# Power.net
KiCad netlist of a schematic drawn in Altium Designer
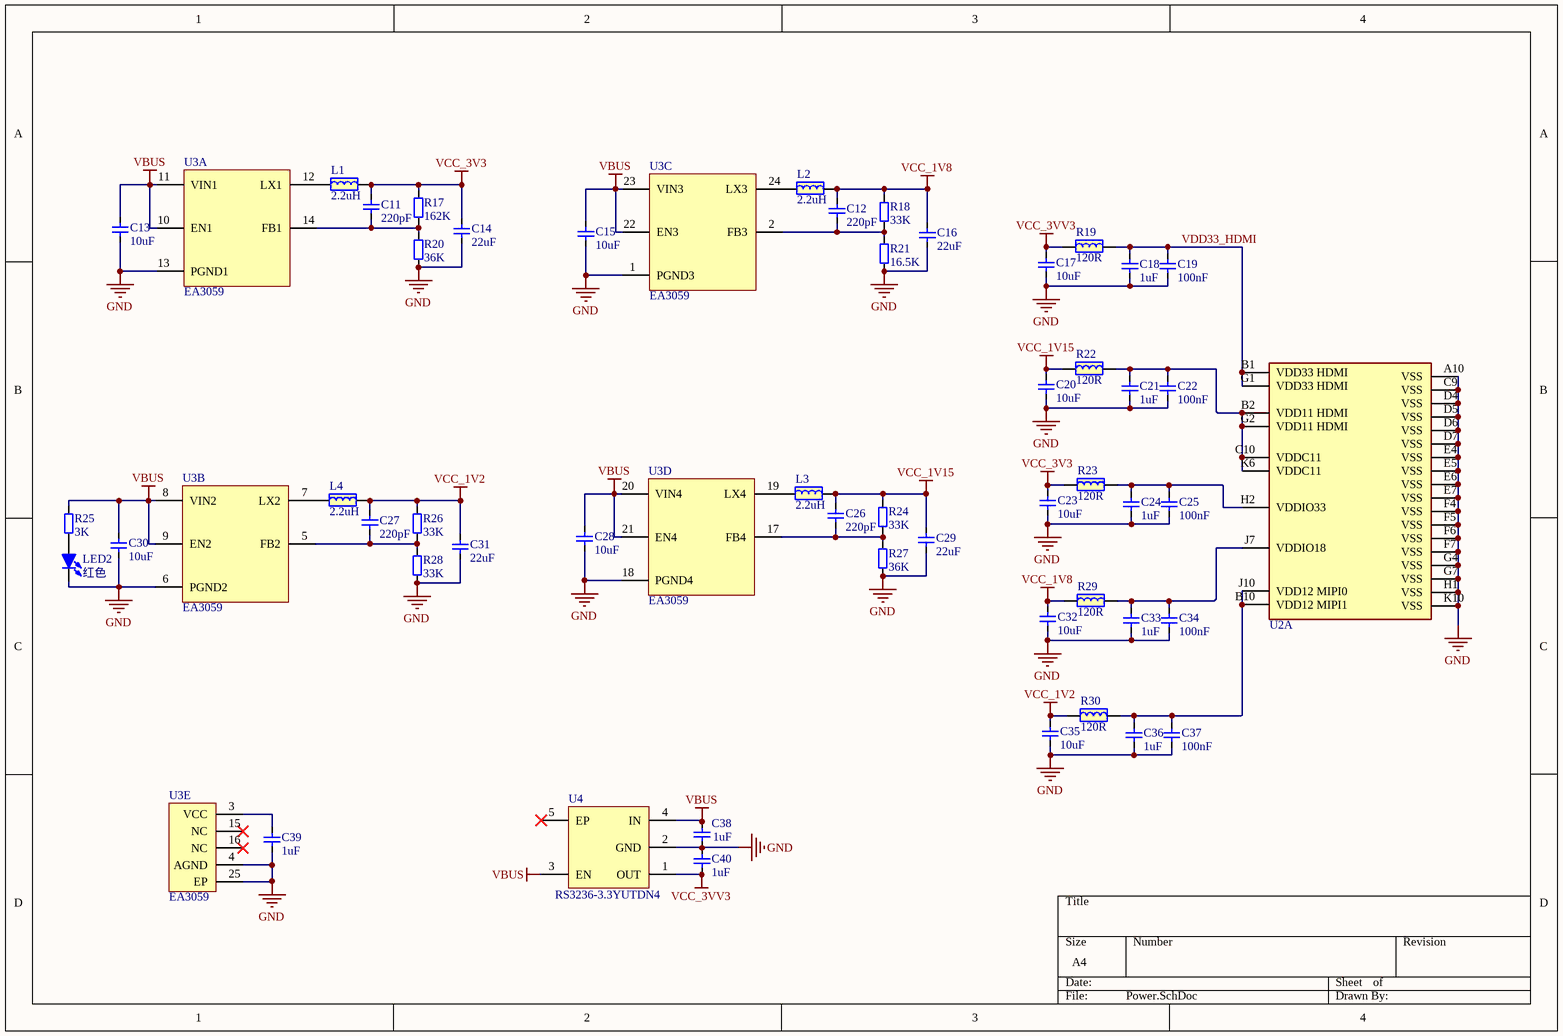
[diagram p0: Power.SchDoc]

(export (version "E")
  (design (tool "Eeschema 10.0.6"))
  (components
    (comp (ref "C11")
      (value "220pF")
      (footprint "C0402_L")
      (description "贴片电容")
      (libsource (lib "0.1 - 电阻-电容-电感-磁珠-电位器") (part "C"))
    )
    (comp (ref "C12")
      (value "220pF")
      (footprint "C0402_L")
      (description "贴片电容")
      (libsource (lib "0.1 - 电阻-电容-电感-磁珠-电位器") (part "C"))
    )
    (comp (ref "C13")
      (value "10uF")
      (footprint "C0402_L")
      (description "贴片电容")
      (libsource (lib "0.1 - 电阻-电容-电感-磁珠-电位器") (part "C"))
    )
    (comp (ref "C14")
      (value "22uF")
      (footprint "C0402_L")
      (description "贴片电容")
      (libsource (lib "0.1 - 电阻-电容-电感-磁珠-电位器") (part "C"))
    )
    (comp (ref "C15")
      (value "10uF")
      (footprint "C0402_L")
      (description "贴片电容")
      (libsource (lib "0.1 - 电阻-电容-电感-磁珠-电位器") (part "C"))
    )
    (comp (ref "C16")
      (value "22uF")
      (footprint "C0402_L")
      (description "贴片电容")
      (libsource (lib "0.1 - 电阻-电容-电感-磁珠-电位器") (part "C"))
    )
    (comp (ref "C17")
      (value "10uF")
      (footprint "C0402_L")
      (description "贴片电容")
      (libsource (lib "0.1 - 电阻-电容-电感-磁珠-电位器") (part "C"))
    )
    (comp (ref "C18")
      (value "1uF")
      (footprint "C0402_L")
      (description "贴片电容")
      (libsource (lib "0.1 - 电阻-电容-电感-磁珠-电位器") (part "C"))
    )
    (comp (ref "C19")
      (value "100nF")
      (footprint "C0402_L")
      (description "贴片电容")
      (libsource (lib "0.1 - 电阻-电容-电感-磁珠-电位器") (part "C"))
    )
    (comp (ref "C20")
      (value "10uF")
      (footprint "C0402_L")
      (description "贴片电容")
      (libsource (lib "0.1 - 电阻-电容-电感-磁珠-电位器") (part "C"))
    )
    (comp (ref "C21")
      (value "1uF")
      (footprint "C0402_L")
      (description "贴片电容")
      (libsource (lib "0.1 - 电阻-电容-电感-磁珠-电位器") (part "C"))
    )
    (comp (ref "C22")
      (value "100nF")
      (footprint "C0402_L")
      (description "贴片电容")
      (libsource (lib "0.1 - 电阻-电容-电感-磁珠-电位器") (part "C"))
    )
    (comp (ref "C23")
      (value "10uF")
      (footprint "C0402_L")
      (description "贴片电容")
      (libsource (lib "0.1 - 电阻-电容-电感-磁珠-电位器") (part "C"))
    )
    (comp (ref "C24")
      (value "1uF")
      (footprint "C0402_L")
      (description "贴片电容")
      (libsource (lib "0.1 - 电阻-电容-电感-磁珠-电位器") (part "C"))
    )
    (comp (ref "C25")
      (value "100nF")
      (footprint "C0402_L")
      (description "贴片电容")
      (libsource (lib "0.1 - 电阻-电容-电感-磁珠-电位器") (part "C"))
    )
    (comp (ref "C26")
      (value "220pF")
      (footprint "C0402_L")
      (description "贴片电容")
      (libsource (lib "0.1 - 电阻-电容-电感-磁珠-电位器") (part "C"))
    )
    (comp (ref "C27")
      (value "220pF")
      (footprint "C0402_L")
      (description "贴片电容")
      (libsource (lib "0.1 - 电阻-电容-电感-磁珠-电位器") (part "C"))
    )
    (comp (ref "C28")
      (value "10uF")
      (footprint "C0402_L")
      (description "贴片电容")
      (libsource (lib "0.1 - 电阻-电容-电感-磁珠-电位器") (part "C"))
    )
    (comp (ref "C29")
      (value "22uF")
      (footprint "C0402_L")
      (description "贴片电容")
      (libsource (lib "0.1 - 电阻-电容-电感-磁珠-电位器") (part "C"))
    )
    (comp (ref "C30")
      (value "10uF")
      (footprint "C0402_L")
      (description "贴片电容")
      (libsource (lib "0.1 - 电阻-电容-电感-磁珠-电位器") (part "C"))
    )
    (comp (ref "C31")
      (value "22uF")
      (footprint "C0402_L")
      (description "贴片电容")
      (libsource (lib "0.1 - 电阻-电容-电感-磁珠-电位器") (part "C"))
    )
    (comp (ref "C32")
      (value "10uF")
      (footprint "C0402_L")
      (description "贴片电容")
      (libsource (lib "0.1 - 电阻-电容-电感-磁珠-电位器") (part "C"))
    )
    (comp (ref "C33")
      (value "1uF")
      (footprint "C0402_L")
      (description "贴片电容")
      (libsource (lib "0.1 - 电阻-电容-电感-磁珠-电位器") (part "C"))
    )
    (comp (ref "C34")
      (value "100nF")
      (footprint "C0402_L")
      (description "贴片电容")
      (libsource (lib "0.1 - 电阻-电容-电感-磁珠-电位器") (part "C"))
    )
    (comp (ref "C35")
      (value "10uF")
      (footprint "C0402_L")
      (description "贴片电容")
      (libsource (lib "0.1 - 电阻-电容-电感-磁珠-电位器") (part "C"))
    )
    (comp (ref "C36")
      (value "1uF")
      (footprint "C0402_L")
      (description "贴片电容")
      (libsource (lib "0.1 - 电阻-电容-电感-磁珠-电位器") (part "C"))
    )
    (comp (ref "C37")
      (value "100nF")
      (footprint "C0402_L")
      (description "贴片电容")
      (libsource (lib "0.1 - 电阻-电容-电感-磁珠-电位器") (part "C"))
    )
    (comp (ref "C38")
      (value "1uF")
      (footprint "C0402_L")
      (description "贴片电容")
      (libsource (lib "0.1 - 电阻-电容-电感-磁珠-电位器") (part "C"))
    )
    (comp (ref "C39")
      (value "1uF")
      (footprint "C0402_L")
      (description "贴片电容")
      (libsource (lib "0.1 - 电阻-电容-电感-磁珠-电位器") (part "C"))
    )
    (comp (ref "C40")
      (value "1uF")
      (footprint "C0402_L")
      (description "贴片电容")
      (libsource (lib "0.1 - 电阻-电容-电感-磁珠-电位器") (part "C"))
    )
    (comp (ref "L1")
      (value "2.2uH")
      (footprint "L0603")
      (description "磁珠")
      (libsource (lib "0.1 - 电阻-电容-电感-磁珠-电位器") (part "L-FB"))
    )
    (comp (ref "L2")
      (value "2.2uH")
      (footprint "L0603")
      (description "磁珠")
      (libsource (lib "0.1 - 电阻-电容-电感-磁珠-电位器") (part "L-FB"))
    )
    (comp (ref "L3")
      (value "2.2uH")
      (footprint "L0603")
      (description "磁珠")
      (libsource (lib "0.1 - 电阻-电容-电感-磁珠-电位器") (part "L-FB"))
    )
    (comp (ref "L4")
      (value "2.2uH")
      (footprint "L0603")
      (description "磁珠")
      (libsource (lib "0.1 - 电阻-电容-电感-磁珠-电位器") (part "L-FB"))
    )
    (comp (ref "LED2")
      (value "红色")
      (footprint "LED0402")
      (description "贴片LED")
      (libsource (lib "0.3 - LED发光二极管") (part "LED-SMD"))
    )
    (comp (ref "R17")
      (value "162K")
      (footprint "R0402_L")
      (description "贴片电阻")
      (libsource (lib "0.1 - 电阻-电容-电感-磁珠-电位器") (part "R"))
    )
    (comp (ref "R18")
      (value "33K")
      (footprint "R0402_L")
      (description "贴片电阻")
      (libsource (lib "0.1 - 电阻-电容-电感-磁珠-电位器") (part "R"))
    )
    (comp (ref "R19")
      (value "120R")
      (footprint "L0402")
      (description "磁珠")
      (libsource (lib "0.1 - 电阻-电容-电感-磁珠-电位器") (part "L-FB"))
    )
    (comp (ref "R20")
      (value "36K")
      (footprint "R0402_L")
      (description "贴片电阻")
      (libsource (lib "0.1 - 电阻-电容-电感-磁珠-电位器") (part "R"))
    )
    (comp (ref "R21")
      (value "16.5K")
      (footprint "R0402_L")
      (description "贴片电阻")
      (libsource (lib "0.1 - 电阻-电容-电感-磁珠-电位器") (part "R"))
    )
    (comp (ref "R22")
      (value "120R")
      (footprint "L0402")
      (description "磁珠")
      (libsource (lib "0.1 - 电阻-电容-电感-磁珠-电位器") (part "L-FB"))
    )
    (comp (ref "R23")
      (value "120R")
      (footprint "L0402")
      (description "磁珠")
      (libsource (lib "0.1 - 电阻-电容-电感-磁珠-电位器") (part "L-FB"))
    )
    (comp (ref "R24")
      (value "33K")
      (footprint "R0402_L")
      (description "贴片电阻")
      (libsource (lib "0.1 - 电阻-电容-电感-磁珠-电位器") (part "R"))
    )
    (comp (ref "R25")
      (value "3K")
      (footprint "R0402_L")
      (description "贴片电阻")
      (libsource (lib "0.1 - 电阻-电容-电感-磁珠-电位器") (part "R"))
    )
    (comp (ref "R26")
      (value "33K")
      (footprint "R0402_L")
      (description "贴片电阻")
      (libsource (lib "0.1 - 电阻-电容-电感-磁珠-电位器") (part "R"))
    )
    (comp (ref "R27")
      (value "36K")
      (footprint "R0402_L")
      (description "贴片电阻")
      (libsource (lib "0.1 - 电阻-电容-电感-磁珠-电位器") (part "R"))
    )
    (comp (ref "R28")
      (value "33K")
      (footprint "R0402_L")
      (description "贴片电阻")
      (libsource (lib "0.1 - 电阻-电容-电感-磁珠-电位器") (part "R"))
    )
    (comp (ref "R29")
      (value "120R")
      (footprint "L0402")
      (description "磁珠")
      (libsource (lib "0.1 - 电阻-电容-电感-磁珠-电位器") (part "L-FB"))
    )
    (comp (ref "R30")
      (value "120R")
      (footprint "L0402")
      (description "磁珠")
      (libsource (lib "0.1 - 电阻-电容-电感-磁珠-电位器") (part "L-FB"))
    )
    (comp (ref "U2")
      (value "TC358870XBG")
      (footprint "TC358870XBG")
      (libsource (lib "User") (part "TC358870XBG"))
    )
    (comp (ref "U3")
      (value "EA3059")
      (footprint "EA3059")
      (description "4CH_BUCK")
      (libsource (lib "User") (part "EA3059"))
    )
    (comp (ref "U4")
      (value "RS3236-3.3YUTDN4")
      (footprint "RS3236-3.3YUTDN4")
      (libsource (lib "User") (part "RS3236-3.3YUTDN4"))
    )
  )
  (nets
    (net (code "1") (name "/VDD33_HDMI") (class "Default")
      (node (ref "C18") (pin "2") (pinfunction "2_2") (pintype "passive"))
      (node (ref "C19") (pin "2") (pinfunction "2_2") (pintype "passive"))
      (node (ref "R19") (pin "2") (pinfunction "2_2") (pintype "passive"))
      (node (ref "U2") (pin "B1") (pinfunction "VDD33_HDMI_B1") (pintype "passive"))
      (node (ref "U2") (pin "G1") (pinfunction "VDD33_HDMI_G1") (pintype "passive"))
    )
    (net (code "2") (name "GND") (class "Default")
      (node (ref "C13") (pin "1") (pinfunction "1_1") (pintype "passive"))
      (node (ref "C14") (pin "1") (pinfunction "1_1") (pintype "passive"))
      (node (ref "C15") (pin "1") (pinfunction "1_1") (pintype "passive"))
      (node (ref "C16") (pin "1") (pinfunction "1_1") (pintype "passive"))
      (node (ref "C17") (pin "1") (pinfunction "1_1") (pintype "passive"))
      (node (ref "C18") (pin "1") (pinfunction "1_1") (pintype "passive"))
      (node (ref "C19") (pin "1") (pinfunction "1_1") (pintype "passive"))
      (node (ref "C20") (pin "1") (pinfunction "1_1") (pintype "passive"))
      (node (ref "C21") (pin "1") (pinfunction "1_1") (pintype "passive"))
      (node (ref "C22") (pin "1") (pinfunction "1_1") (pintype "passive"))
      (node (ref "C23") (pin "1") (pinfunction "1_1") (pintype "passive"))
      (node (ref "C24") (pin "1") (pinfunction "1_1") (pintype "passive"))
      (node (ref "C25") (pin "1") (pinfunction "1_1") (pintype "passive"))
      (node (ref "C28") (pin "1") (pinfunction "1_1") (pintype "passive"))
      (node (ref "C29") (pin "1") (pinfunction "1_1") (pintype "passive"))
      (node (ref "C30") (pin "1") (pinfunction "1_1") (pintype "passive"))
      (node (ref "C31") (pin "1") (pinfunction "1_1") (pintype "passive"))
      (node (ref "C32") (pin "1") (pinfunction "1_1") (pintype "passive"))
      (node (ref "C33") (pin "1") (pinfunction "1_1") (pintype "passive"))
      (node (ref "C34") (pin "1") (pinfunction "1_1") (pintype "passive"))
      (node (ref "C35") (pin "1") (pinfunction "1_1") (pintype "passive"))
      (node (ref "C36") (pin "1") (pinfunction "1_1") (pintype "passive"))
      (node (ref "C37") (pin "1") (pinfunction "1_1") (pintype "passive"))
      (node (ref "C38") (pin "1") (pinfunction "1_1") (pintype "passive"))
      (node (ref "C39") (pin "1") (pinfunction "1_1") (pintype "passive"))
      (node (ref "C40") (pin "2") (pinfunction "2_2") (pintype "passive"))
      (node (ref "LED2") (pin "2") (pinfunction "K_2") (pintype "passive"))
      (node (ref "R20") (pin "1") (pinfunction "1_1") (pintype "passive"))
      (node (ref "R21") (pin "1") (pinfunction "1_1") (pintype "passive"))
      (node (ref "R27") (pin "1") (pinfunction "1_1") (pintype "passive"))
      (node (ref "R28") (pin "1") (pinfunction "1_1") (pintype "passive"))
      (node (ref "U2") (pin "A10") (pinfunction "VSS_A10") (pintype "passive"))
      (node (ref "U2") (pin "C9") (pinfunction "VSS_C9") (pintype "passive"))
      (node (ref "U2") (pin "D4") (pinfunction "VSS_D4") (pintype "passive"))
      (node (ref "U2") (pin "D5") (pinfunction "VSS_D5") (pintype "passive"))
      (node (ref "U2") (pin "D6") (pinfunction "VSS_D6") (pintype "passive"))
      (node (ref "U2") (pin "D7") (pinfunction "VSS_D7") (pintype "passive"))
      (node (ref "U2") (pin "E4") (pinfunction "VSS_E4") (pintype "passive"))
      (node (ref "U2") (pin "E5") (pinfunction "VSS_E5") (pintype "passive"))
      (node (ref "U2") (pin "E6") (pinfunction "VSS_E6") (pintype "passive"))
      (node (ref "U2") (pin "E7") (pinfunction "VSS_E7") (pintype "passive"))
      (node (ref "U2") (pin "F4") (pinfunction "VSS_F4") (pintype "passive"))
      (node (ref "U2") (pin "F5") (pinfunction "VSS_F5") (pintype "passive"))
      (node (ref "U2") (pin "F6") (pinfunction "VSS_F6") (pintype "passive"))
      (node (ref "U2") (pin "F7") (pinfunction "VSS_F7") (pintype "passive"))
      (node (ref "U2") (pin "G4") (pinfunction "VSS_G4") (pintype "passive"))
      (node (ref "U2") (pin "G7") (pinfunction "VSS_G7") (pintype "passive"))
      (node (ref "U2") (pin "H1") (pinfunction "VSS_H1") (pintype "passive"))
      (node (ref "U2") (pin "K10") (pinfunction "VSS_K10") (pintype "passive"))
      (node (ref "U3") (pin "1") (pinfunction "PGND3_1") (pintype "passive"))
      (node (ref "U3") (pin "13") (pinfunction "PGND1_13") (pintype "passive"))
      (node (ref "U3") (pin "18") (pinfunction "PGND4_18") (pintype "passive"))
      (node (ref "U3") (pin "25") (pinfunction "EP_25") (pintype "passive"))
      (node (ref "U3") (pin "4") (pinfunction "AGND_4") (pintype "passive"))
      (node (ref "U3") (pin "6") (pinfunction "PGND2_6") (pintype "passive"))
      (node (ref "U4") (pin "2") (pinfunction "GND_2") (pintype "passive"))
    )
    (net (code "3") (name "Net-(C21-Pad2)") (class "Default")
      (node (ref "C21") (pin "2") (pinfunction "2_2") (pintype "passive"))
      (node (ref "C22") (pin "2") (pinfunction "2_2") (pintype "passive"))
      (node (ref "R22") (pin "2") (pinfunction "2_2") (pintype "passive"))
      (node (ref "U2") (pin "B2") (pinfunction "VDD11_HDMI_B2") (pintype "passive"))
      (node (ref "U2") (pin "C10") (pinfunction "VDDC11_C10") (pintype "passive"))
      (node (ref "U2") (pin "G2") (pinfunction "VDD11_HDMI_G2") (pintype "passive"))
      (node (ref "U2") (pin "K6") (pinfunction "VDDC11_K6") (pintype "passive"))
    )
    (net (code "4") (name "Net-(LED2-A)") (class "Default")
      (node (ref "LED2") (pin "1") (pinfunction "A_1") (pintype "passive"))
      (node (ref "R25") (pin "1") (pinfunction "1_1") (pintype "passive"))
    )
    (net (code "5") (name "Net-(U2A-VDD12_MIPI0)") (class "Default")
      (node (ref "C36") (pin "2") (pinfunction "2_2") (pintype "passive"))
      (node (ref "C37") (pin "2") (pinfunction "2_2") (pintype "passive"))
      (node (ref "R30") (pin "2") (pinfunction "2_2") (pintype "passive"))
      (node (ref "U2") (pin "B10") (pinfunction "VDD12_MIPI1_B10") (pintype "passive"))
      (node (ref "U2") (pin "J10") (pinfunction "VDD12_MIPI0_J10") (pintype "passive"))
    )
    (net (code "6") (name "Net-(U2A-VDDIO18)") (class "Default")
      (node (ref "C33") (pin "2") (pinfunction "2_2") (pintype "passive"))
      (node (ref "C34") (pin "2") (pinfunction "2_2") (pintype "passive"))
      (node (ref "R29") (pin "2") (pinfunction "2_2") (pintype "passive"))
      (node (ref "U2") (pin "J7") (pinfunction "VDDIO18_J7") (pintype "passive"))
    )
    (net (code "7") (name "Net-(U2A-VDDIO33)") (class "Default")
      (node (ref "C24") (pin "2") (pinfunction "2_2") (pintype "passive"))
      (node (ref "C25") (pin "2") (pinfunction "2_2") (pintype "passive"))
      (node (ref "R23") (pin "2") (pinfunction "2_2") (pintype "passive"))
      (node (ref "U2") (pin "H2") (pinfunction "VDDIO33_H2") (pintype "passive"))
    )
    (net (code "8") (name "Net-(U3A-FB1)") (class "Default")
      (node (ref "C11") (pin "1") (pinfunction "1_1") (pintype "passive"))
      (node (ref "R17") (pin "1") (pinfunction "1_1") (pintype "passive"))
      (node (ref "R20") (pin "2") (pinfunction "2_2") (pintype "passive"))
      (node (ref "U3") (pin "14") (pinfunction "FB1_14") (pintype "passive"))
    )
    (net (code "9") (name "Net-(U3A-LX1)") (class "Default")
      (node (ref "L1") (pin "1") (pintype "passive"))
      (node (ref "U3") (pin "12") (pinfunction "LX1_12") (pintype "passive"))
    )
    (net (code "10") (name "Net-(U3B-FB2)") (class "Default")
      (node (ref "C27") (pin "1") (pinfunction "1_1") (pintype "passive"))
      (node (ref "R26") (pin "1") (pinfunction "1_1") (pintype "passive"))
      (node (ref "R28") (pin "2") (pinfunction "2_2") (pintype "passive"))
      (node (ref "U3") (pin "5") (pinfunction "FB2_5") (pintype "passive"))
    )
    (net (code "11") (name "Net-(U3B-LX2)") (class "Default")
      (node (ref "L4") (pin "1") (pintype "passive"))
      (node (ref "U3") (pin "7") (pinfunction "LX2_7") (pintype "passive"))
    )
    (net (code "12") (name "Net-(U3C-FB3)") (class "Default")
      (node (ref "C12") (pin "1") (pinfunction "1_1") (pintype "passive"))
      (node (ref "R18") (pin "1") (pinfunction "1_1") (pintype "passive"))
      (node (ref "R21") (pin "2") (pinfunction "2_2") (pintype "passive"))
      (node (ref "U3") (pin "2") (pinfunction "FB3_2") (pintype "passive"))
    )
    (net (code "13") (name "Net-(U3C-LX3)") (class "Default")
      (node (ref "L2") (pin "1") (pintype "passive"))
      (node (ref "U3") (pin "24") (pinfunction "LX3_24") (pintype "passive"))
    )
    (net (code "14") (name "Net-(U3D-FB4)") (class "Default")
      (node (ref "C26") (pin "1") (pinfunction "1_1") (pintype "passive"))
      (node (ref "R24") (pin "1") (pinfunction "1_1") (pintype "passive"))
      (node (ref "R27") (pin "2") (pinfunction "2_2") (pintype "passive"))
      (node (ref "U3") (pin "17") (pinfunction "FB4_17") (pintype "passive"))
    )
    (net (code "15") (name "Net-(U3D-LX4)") (class "Default")
      (node (ref "L3") (pin "1") (pintype "passive"))
      (node (ref "U3") (pin "19") (pinfunction "LX4_19") (pintype "passive"))
    )
    (net (code "16") (name "Net-(U3E-VCC)") (class "Default")
      (node (ref "C39") (pin "2") (pinfunction "2_2") (pintype "passive"))
      (node (ref "U3") (pin "3") (pinfunction "VCC_3") (pintype "passive"))
    )
    (net (code "17") (name "VBUS") (class "Default")
      (node (ref "C13") (pin "2") (pinfunction "2_2") (pintype "passive"))
      (node (ref "C15") (pin "2") (pinfunction "2_2") (pintype "passive"))
      (node (ref "C28") (pin "2") (pinfunction "2_2") (pintype "passive"))
      (node (ref "C30") (pin "2") (pinfunction "2_2") (pintype "passive"))
      (node (ref "C38") (pin "2") (pinfunction "2_2") (pintype "passive"))
      (node (ref "R25") (pin "2") (pinfunction "2_2") (pintype "passive"))
      (node (ref "U3") (pin "10") (pinfunction "EN1_10") (pintype "passive"))
      (node (ref "U3") (pin "11") (pinfunction "VIN1_11") (pintype "passive"))
      (node (ref "U3") (pin "20") (pinfunction "VIN4_20") (pintype "passive"))
      (node (ref "U3") (pin "21") (pinfunction "EN4_21") (pintype "passive"))
      (node (ref "U3") (pin "22") (pinfunction "EN3_22") (pintype "passive"))
      (node (ref "U3") (pin "23") (pinfunction "VIN3_23") (pintype "passive"))
      (node (ref "U3") (pin "8") (pinfunction "VIN2_8") (pintype "passive"))
      (node (ref "U3") (pin "9") (pinfunction "EN2_9") (pintype "passive"))
      (node (ref "U4") (pin "3") (pinfunction "EN_3") (pintype "passive"))
      (node (ref "U4") (pin "4") (pinfunction "IN_4") (pintype "passive"))
    )
    (net (code "18") (name "VCC_1V2") (class "Default")
      (node (ref "C27") (pin "2") (pinfunction "2_2") (pintype "passive"))
      (node (ref "C31") (pin "2") (pinfunction "2_2") (pintype "passive"))
      (node (ref "C35") (pin "2") (pinfunction "2_2") (pintype "passive"))
      (node (ref "L4") (pin "2") (pinfunction "2_2") (pintype "passive"))
      (node (ref "R26") (pin "2") (pinfunction "2_2") (pintype "passive"))
      (node (ref "R30") (pin "1") (pintype "passive"))
    )
    (net (code "19") (name "VCC_1V8") (class "Default")
      (node (ref "C12") (pin "2") (pinfunction "2_2") (pintype "passive"))
      (node (ref "C16") (pin "2") (pinfunction "2_2") (pintype "passive"))
      (node (ref "C32") (pin "2") (pinfunction "2_2") (pintype "passive"))
      (node (ref "L2") (pin "2") (pinfunction "2_2") (pintype "passive"))
      (node (ref "R18") (pin "2") (pinfunction "2_2") (pintype "passive"))
      (node (ref "R29") (pin "1") (pintype "passive"))
    )
    (net (code "20") (name "VCC_1V15") (class "Default")
      (node (ref "C20") (pin "2") (pinfunction "2_2") (pintype "passive"))
      (node (ref "C26") (pin "2") (pinfunction "2_2") (pintype "passive"))
      (node (ref "C29") (pin "2") (pinfunction "2_2") (pintype "passive"))
      (node (ref "L3") (pin "2") (pinfunction "2_2") (pintype "passive"))
      (node (ref "R22") (pin "1") (pintype "passive"))
      (node (ref "R24") (pin "2") (pinfunction "2_2") (pintype "passive"))
    )
    (net (code "21") (name "VCC_3V3") (class "Default")
      (node (ref "C11") (pin "2") (pinfunction "2_2") (pintype "passive"))
      (node (ref "C14") (pin "2") (pinfunction "2_2") (pintype "passive"))
      (node (ref "C23") (pin "2") (pinfunction "2_2") (pintype "passive"))
      (node (ref "L1") (pin "2") (pinfunction "2_2") (pintype "passive"))
      (node (ref "R17") (pin "2") (pinfunction "2_2") (pintype "passive"))
      (node (ref "R23") (pin "1") (pintype "passive"))
    )
    (net (code "22") (name "VCC_3VV3") (class "Default")
      (node (ref "C17") (pin "2") (pinfunction "2_2") (pintype "passive"))
      (node (ref "C40") (pin "1") (pinfunction "1_1") (pintype "passive"))
      (node (ref "R19") (pin "1") (pintype "passive"))
      (node (ref "U4") (pin "1") (pinfunction "OUT_1") (pintype "passive"))
    )
    (net (code "23") (name "unconnected-(U3E-NC-Pad15)") (class "Default")
      (node (ref "U3") (pin "15") (pinfunction "NC_15") (pintype "passive+no_connect"))
    )
    (net (code "24") (name "unconnected-(U3E-NC-Pad16)") (class "Default")
      (node (ref "U3") (pin "16") (pinfunction "NC_16") (pintype "passive+no_connect"))
    )
    (net (code "25") (name "unconnected-(U4-EP-Pad5)") (class "Default")
      (node (ref "U4") (pin "5") (pinfunction "EP_5") (pintype "passive+no_connect"))
    )
  )
)
